# Sheet_1_2023-02-11.net
KiCad netlist of a schematic drawn in Altium Designer
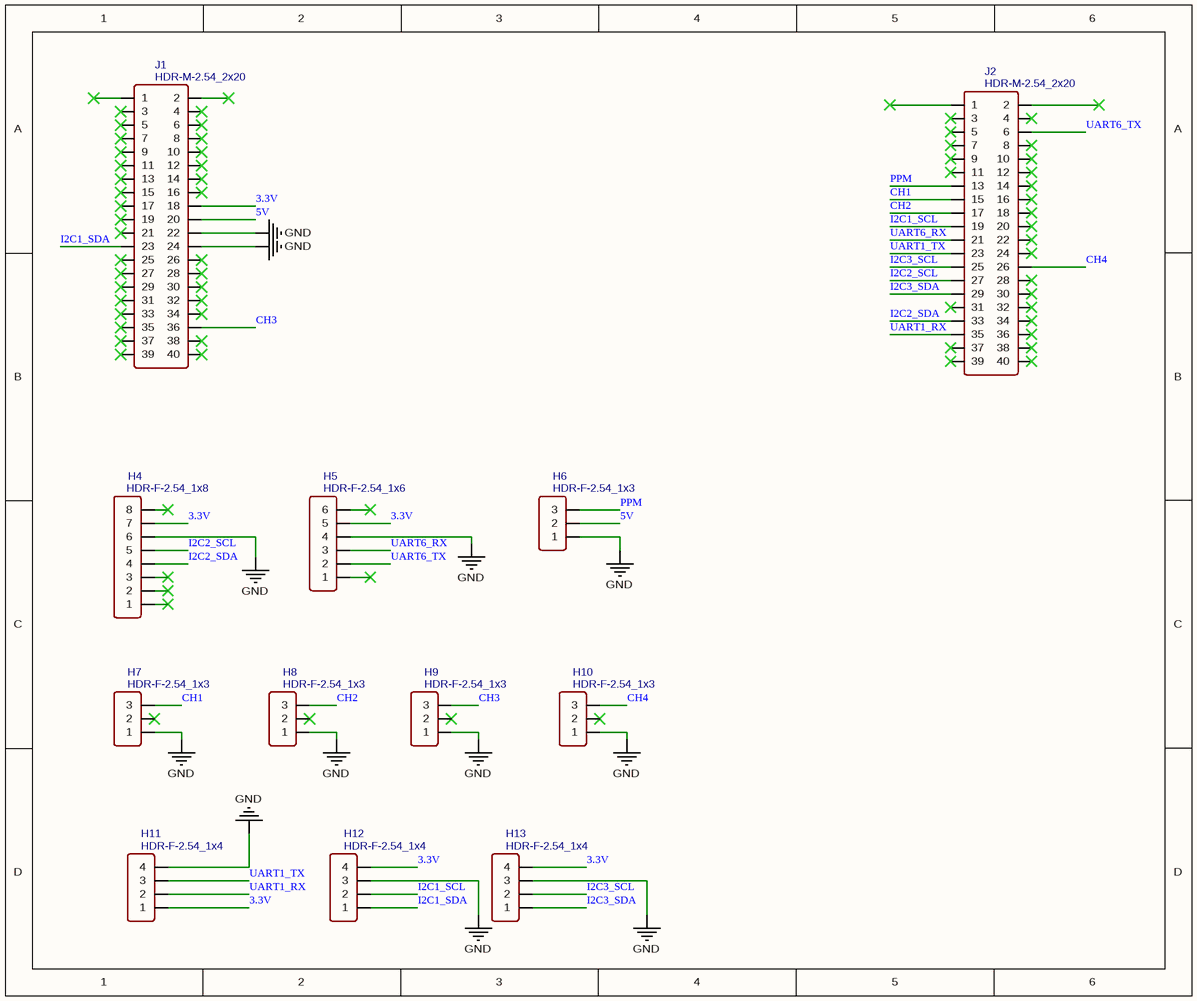
[diagram p0: Sheet_1_2023-02-11.schdoc]

(export (version "E")
  (design (tool "Eeschema 10.0.6"))
  (components
    (comp (ref "H4")
      (value "HDR-F-2.54_1x8")
      (fields (field (name "BOM_SUPPLIER PART") "C225505") (field (name "CONTRIBUTOR") "LCEDA_Lib"))
      (libsource (lib "altium-import") (part "root_2_HDR-F-2.54_1x8_"))
    )
    (comp (ref "H5")
      (value "HDR-F-2.54_1x6")
      (fields (field (name "BOM_SUPPLIER PART") "C40877") (field (name "CONTRIBUTOR") "LCEDA_Lib"))
      (libsource (lib "altium-import") (part "root_2_HDR-F-2.54_1x6_"))
    )
    (comp (ref "H6")
      (value "HDR-F-2.54_1x3")
      (fields (field (name "BOM_SUPPLIER PART") "C146690") (field (name "CONTRIBUTOR") "LCEDA_Lib"))
      (libsource (lib "altium-import") (part "root_2_HDR-F-2.54_1x3_"))
    )
    (comp (ref "H7")
      (value "HDR-F-2.54_1x3")
      (fields (field (name "BOM_SUPPLIER PART") "C146690") (field (name "CONTRIBUTOR") "LCEDA_Lib"))
      (libsource (lib "altium-import") (part "root_2_HDR-F-2.54_1x3_"))
    )
    (comp (ref "H8")
      (value "HDR-F-2.54_1x3")
      (fields (field (name "BOM_SUPPLIER PART") "C146690") (field (name "CONTRIBUTOR") "LCEDA_Lib"))
      (libsource (lib "altium-import") (part "root_2_HDR-F-2.54_1x3_"))
    )
    (comp (ref "H9")
      (value "HDR-F-2.54_1x3")
      (fields (field (name "BOM_SUPPLIER PART") "C146690") (field (name "CONTRIBUTOR") "LCEDA_Lib"))
      (libsource (lib "altium-import") (part "root_2_HDR-F-2.54_1x3_"))
    )
    (comp (ref "H10")
      (value "HDR-F-2.54_1x3")
      (fields (field (name "BOM_SUPPLIER PART") "C146690") (field (name "CONTRIBUTOR") "LCEDA_Lib"))
      (libsource (lib "altium-import") (part "root_2_HDR-F-2.54_1x3_"))
    )
    (comp (ref "H11")
      (value "HDR-F-2.54_1x4")
      (fields (field (name "BOM_SUPPLIER PART") "C225501") (field (name "CONTRIBUTOR") "LCEDA_Lib"))
      (libsource (lib "altium-import") (part "root_2_HDR-F-2.54_1x4_"))
    )
    (comp (ref "H12")
      (value "HDR-F-2.54_1x4")
      (fields (field (name "BOM_SUPPLIER PART") "C225501") (field (name "CONTRIBUTOR") "LCEDA_Lib"))
      (libsource (lib "altium-import") (part "root_2_HDR-F-2.54_1x4_"))
    )
    (comp (ref "H13")
      (value "HDR-F-2.54_1x4")
      (fields (field (name "BOM_SUPPLIER PART") "C225501") (field (name "CONTRIBUTOR") "LCEDA_Lib"))
      (libsource (lib "altium-import") (part "root_2_HDR-F-2.54_1x4_"))
    )
    (comp (ref "J1")
      (value "HDR-M-2.54_2x20")
      (fields (field (name "BOM_SUPPLIER PART") "C50980") (field (name "CONTRIBUTOR") "LCEDA_Lib"))
      (libsource (lib "altium-import") (part "root_0_HDR-M-2.54_2x20_"))
    )
    (comp (ref "J2")
      (value "HDR-M-2.54_2x20")
      (fields (field (name "BOM_SUPPLIER PART") "C50980") (field (name "CONTRIBUTOR") "LCEDA_Lib"))
      (libsource (lib "altium-import") (part "root_0_HDR-M-2.54_2x20_"))
    )
  )
  (nets
    (net (code "1") (name "/3.3V") (class "Default")
      (node (ref "H11") (pin "1") (pinfunction "1_1") (pintype "passive"))
      (node (ref "H12") (pin "4") (pinfunction "4_4") (pintype "passive"))
      (node (ref "H13") (pin "4") (pinfunction "4_4") (pintype "passive"))
      (node (ref "H4") (pin "7") (pinfunction "7_7") (pintype "passive"))
      (node (ref "H5") (pin "5") (pinfunction "5_5") (pintype "passive"))
      (node (ref "J1") (pin "18") (pinfunction "18_18") (pintype "passive"))
    )
    (net (code "2") (name "/5V") (class "Default")
      (node (ref "H6") (pin "2") (pinfunction "2_2") (pintype "passive"))
      (node (ref "J1") (pin "20") (pinfunction "20_20") (pintype "passive"))
    )
    (net (code "3") (name "/CH1") (class "Default")
      (node (ref "H7") (pin "3") (pinfunction "3_3") (pintype "passive"))
      (node (ref "J2") (pin "15") (pinfunction "15_15") (pintype "passive"))
    )
    (net (code "4") (name "/CH2") (class "Default")
      (node (ref "H8") (pin "3") (pinfunction "3_3") (pintype "passive"))
      (node (ref "J2") (pin "17") (pinfunction "17_17") (pintype "passive"))
    )
    (net (code "5") (name "/CH3") (class "Default")
      (node (ref "H9") (pin "3") (pinfunction "3_3") (pintype "passive"))
      (node (ref "J1") (pin "36") (pinfunction "36_36") (pintype "passive"))
    )
    (net (code "6") (name "/CH4") (class "Default")
      (node (ref "H10") (pin "3") (pinfunction "3_3") (pintype "passive"))
      (node (ref "J2") (pin "26") (pinfunction "26_26") (pintype "passive"))
    )
    (net (code "7") (name "/I2C1_SCL") (class "Default")
      (node (ref "H12") (pin "2") (pinfunction "2_2") (pintype "passive"))
      (node (ref "J2") (pin "19") (pinfunction "19_19") (pintype "passive"))
    )
    (net (code "8") (name "/I2C1_SDA") (class "Default")
      (node (ref "H12") (pin "1") (pinfunction "1_1") (pintype "passive"))
      (node (ref "J1") (pin "23") (pinfunction "23_23") (pintype "passive"))
    )
    (net (code "9") (name "/I2C2_SCL") (class "Default")
      (node (ref "H4") (pin "5") (pinfunction "5_5") (pintype "passive"))
      (node (ref "J2") (pin "27") (pinfunction "27_27") (pintype "passive"))
    )
    (net (code "10") (name "/I2C2_SDA") (class "Default")
      (node (ref "H4") (pin "4") (pinfunction "4_4") (pintype "passive"))
      (node (ref "J2") (pin "33") (pinfunction "33_33") (pintype "passive"))
    )
    (net (code "11") (name "/I2C3_SCL") (class "Default")
      (node (ref "H13") (pin "2") (pinfunction "2_2") (pintype "passive"))
      (node (ref "J2") (pin "25") (pinfunction "25_25") (pintype "passive"))
    )
    (net (code "12") (name "/I2C3_SDA") (class "Default")
      (node (ref "H13") (pin "1") (pinfunction "1_1") (pintype "passive"))
      (node (ref "J2") (pin "29") (pinfunction "29_29") (pintype "passive"))
    )
    (net (code "13") (name "/PPM") (class "Default")
      (node (ref "H6") (pin "3") (pinfunction "3_3") (pintype "passive"))
      (node (ref "J2") (pin "13") (pinfunction "13_13") (pintype "passive"))
    )
    (net (code "14") (name "/UART1_RX") (class "Default")
      (node (ref "H11") (pin "2") (pinfunction "2_2") (pintype "passive"))
      (node (ref "J2") (pin "35") (pinfunction "35_35") (pintype "passive"))
    )
    (net (code "15") (name "/UART1_TX") (class "Default")
      (node (ref "H11") (pin "3") (pinfunction "3_3") (pintype "passive"))
      (node (ref "J2") (pin "23") (pinfunction "23_23") (pintype "passive"))
    )
    (net (code "16") (name "/UART6_RX") (class "Default")
      (node (ref "H5") (pin "3") (pinfunction "3_3") (pintype "passive"))
      (node (ref "J2") (pin "21") (pinfunction "21_21") (pintype "passive"))
    )
    (net (code "17") (name "/UART6_TX") (class "Default")
      (node (ref "H5") (pin "2") (pinfunction "2_2") (pintype "passive"))
      (node (ref "J2") (pin "6") (pinfunction "6_6") (pintype "passive"))
    )
    (net (code "18") (name "GND") (class "Default")
      (node (ref "H10") (pin "1") (pinfunction "1_1") (pintype "passive"))
      (node (ref "H11") (pin "4") (pinfunction "4_4") (pintype "passive"))
      (node (ref "H12") (pin "3") (pinfunction "3_3") (pintype "passive"))
      (node (ref "H13") (pin "3") (pinfunction "3_3") (pintype "passive"))
      (node (ref "H4") (pin "6") (pinfunction "6_6") (pintype "passive"))
      (node (ref "H5") (pin "4") (pinfunction "4_4") (pintype "passive"))
      (node (ref "H6") (pin "1") (pinfunction "1_1") (pintype "passive"))
      (node (ref "H7") (pin "1") (pinfunction "1_1") (pintype "passive"))
      (node (ref "H8") (pin "1") (pinfunction "1_1") (pintype "passive"))
      (node (ref "H9") (pin "1") (pinfunction "1_1") (pintype "passive"))
      (node (ref "J1") (pin "22") (pinfunction "22_22") (pintype "passive"))
      (node (ref "J1") (pin "24") (pinfunction "24_24") (pintype "passive"))
    )
    (net (code "19") (name "unconnected-(H4-Pad1)") (class "Default")
      (node (ref "H4") (pin "1") (pinfunction "1_1") (pintype "passive+no_connect"))
    )
    (net (code "20") (name "unconnected-(H4-Pad2)") (class "Default")
      (node (ref "H4") (pin "2") (pinfunction "2_2") (pintype "passive+no_connect"))
    )
    (net (code "21") (name "unconnected-(H4-Pad3)") (class "Default")
      (node (ref "H4") (pin "3") (pinfunction "3_3") (pintype "passive+no_connect"))
    )
    (net (code "22") (name "unconnected-(H4-Pad8)") (class "Default")
      (node (ref "H4") (pin "8") (pinfunction "8_8") (pintype "passive+no_connect"))
    )
    (net (code "23") (name "unconnected-(H5-Pad1)") (class "Default")
      (node (ref "H5") (pin "1") (pinfunction "1_1") (pintype "passive+no_connect"))
    )
    (net (code "24") (name "unconnected-(H5-Pad6)") (class "Default")
      (node (ref "H5") (pin "6") (pinfunction "6_6") (pintype "passive+no_connect"))
    )
    (net (code "25") (name "unconnected-(H7-Pad2)") (class "Default")
      (node (ref "H7") (pin "2") (pinfunction "2_2") (pintype "passive+no_connect"))
    )
    (net (code "26") (name "unconnected-(H8-Pad2)") (class "Default")
      (node (ref "H8") (pin "2") (pinfunction "2_2") (pintype "passive+no_connect"))
    )
    (net (code "27") (name "unconnected-(H9-Pad2)") (class "Default")
      (node (ref "H9") (pin "2") (pinfunction "2_2") (pintype "passive+no_connect"))
    )
    (net (code "28") (name "unconnected-(H10-Pad2)") (class "Default")
      (node (ref "H10") (pin "2") (pinfunction "2_2") (pintype "passive+no_connect"))
    )
    (net (code "29") (name "unconnected-(J1-Pad1)") (class "Default")
      (node (ref "J1") (pin "1") (pinfunction "1_1") (pintype "passive+no_connect"))
    )
    (net (code "30") (name "unconnected-(J1-Pad2)") (class "Default")
      (node (ref "J1") (pin "2") (pinfunction "2_2") (pintype "passive+no_connect"))
    )
    (net (code "31") (name "unconnected-(J1-Pad3)") (class "Default")
      (node (ref "J1") (pin "3") (pinfunction "3_3") (pintype "passive+no_connect"))
    )
    (net (code "32") (name "unconnected-(J1-Pad4)") (class "Default")
      (node (ref "J1") (pin "4") (pinfunction "4_4") (pintype "passive+no_connect"))
    )
    (net (code "33") (name "unconnected-(J1-Pad5)") (class "Default")
      (node (ref "J1") (pin "5") (pinfunction "5_5") (pintype "passive+no_connect"))
    )
    (net (code "34") (name "unconnected-(J1-Pad6)") (class "Default")
      (node (ref "J1") (pin "6") (pinfunction "6_6") (pintype "passive+no_connect"))
    )
    (net (code "35") (name "unconnected-(J1-Pad7)") (class "Default")
      (node (ref "J1") (pin "7") (pinfunction "7_7") (pintype "passive+no_connect"))
    )
    (net (code "36") (name "unconnected-(J1-Pad8)") (class "Default")
      (node (ref "J1") (pin "8") (pinfunction "8_8") (pintype "passive+no_connect"))
    )
    (net (code "37") (name "unconnected-(J1-Pad9)") (class "Default")
      (node (ref "J1") (pin "9") (pinfunction "9_9") (pintype "passive+no_connect"))
    )
    (net (code "38") (name "unconnected-(J1-Pad10)") (class "Default")
      (node (ref "J1") (pin "10") (pinfunction "10_10") (pintype "passive+no_connect"))
    )
    (net (code "39") (name "unconnected-(J1-Pad11)") (class "Default")
      (node (ref "J1") (pin "11") (pinfunction "11_11") (pintype "passive+no_connect"))
    )
    (net (code "40") (name "unconnected-(J1-Pad12)") (class "Default")
      (node (ref "J1") (pin "12") (pinfunction "12_12") (pintype "passive+no_connect"))
    )
    (net (code "41") (name "unconnected-(J1-Pad13)") (class "Default")
      (node (ref "J1") (pin "13") (pinfunction "13_13") (pintype "passive+no_connect"))
    )
    (net (code "42") (name "unconnected-(J1-Pad14)") (class "Default")
      (node (ref "J1") (pin "14") (pinfunction "14_14") (pintype "passive+no_connect"))
    )
    (net (code "43") (name "unconnected-(J1-Pad15)") (class "Default")
      (node (ref "J1") (pin "15") (pinfunction "15_15") (pintype "passive+no_connect"))
    )
    (net (code "44") (name "unconnected-(J1-Pad16)") (class "Default")
      (node (ref "J1") (pin "16") (pinfunction "16_16") (pintype "passive+no_connect"))
    )
    (net (code "45") (name "unconnected-(J1-Pad17)") (class "Default")
      (node (ref "J1") (pin "17") (pinfunction "17_17") (pintype "passive+no_connect"))
    )
    (net (code "46") (name "unconnected-(J1-Pad19)") (class "Default")
      (node (ref "J1") (pin "19") (pinfunction "19_19") (pintype "passive+no_connect"))
    )
    (net (code "47") (name "unconnected-(J1-Pad21)") (class "Default")
      (node (ref "J1") (pin "21") (pinfunction "21_21") (pintype "passive+no_connect"))
    )
    (net (code "48") (name "unconnected-(J1-Pad25)") (class "Default")
      (node (ref "J1") (pin "25") (pinfunction "25_25") (pintype "passive+no_connect"))
    )
    (net (code "49") (name "unconnected-(J1-Pad26)") (class "Default")
      (node (ref "J1") (pin "26") (pinfunction "26_26") (pintype "passive+no_connect"))
    )
    (net (code "50") (name "unconnected-(J1-Pad27)") (class "Default")
      (node (ref "J1") (pin "27") (pinfunction "27_27") (pintype "passive+no_connect"))
    )
    (net (code "51") (name "unconnected-(J1-Pad28)") (class "Default")
      (node (ref "J1") (pin "28") (pinfunction "28_28") (pintype "passive+no_connect"))
    )
    (net (code "52") (name "unconnected-(J1-Pad29)") (class "Default")
      (node (ref "J1") (pin "29") (pinfunction "29_29") (pintype "passive+no_connect"))
    )
    (net (code "53") (name "unconnected-(J1-Pad30)") (class "Default")
      (node (ref "J1") (pin "30") (pinfunction "30_30") (pintype "passive+no_connect"))
    )
    (net (code "54") (name "unconnected-(J1-Pad31)") (class "Default")
      (node (ref "J1") (pin "31") (pinfunction "31_31") (pintype "passive+no_connect"))
    )
    (net (code "55") (name "unconnected-(J1-Pad32)") (class "Default")
      (node (ref "J1") (pin "32") (pinfunction "32_32") (pintype "passive+no_connect"))
    )
    (net (code "56") (name "unconnected-(J1-Pad33)") (class "Default")
      (node (ref "J1") (pin "33") (pinfunction "33_33") (pintype "passive+no_connect"))
    )
    (net (code "57") (name "unconnected-(J1-Pad34)") (class "Default")
      (node (ref "J1") (pin "34") (pinfunction "34_34") (pintype "passive+no_connect"))
    )
    (net (code "58") (name "unconnected-(J1-Pad35)") (class "Default")
      (node (ref "J1") (pin "35") (pinfunction "35_35") (pintype "passive+no_connect"))
    )
    (net (code "59") (name "unconnected-(J1-Pad37)") (class "Default")
      (node (ref "J1") (pin "37") (pinfunction "37_37") (pintype "passive+no_connect"))
    )
    (net (code "60") (name "unconnected-(J1-Pad38)") (class "Default")
      (node (ref "J1") (pin "38") (pinfunction "38_38") (pintype "passive+no_connect"))
    )
    (net (code "61") (name "unconnected-(J1-Pad39)") (class "Default")
      (node (ref "J1") (pin "39") (pinfunction "39_39") (pintype "passive+no_connect"))
    )
    (net (code "62") (name "unconnected-(J1-Pad40)") (class "Default")
      (node (ref "J1") (pin "40") (pinfunction "40_40") (pintype "passive+no_connect"))
    )
    (net (code "63") (name "unconnected-(J2-Pad1)") (class "Default")
      (node (ref "J2") (pin "1") (pinfunction "1_1") (pintype "passive+no_connect"))
    )
    (net (code "64") (name "unconnected-(J2-Pad2)") (class "Default")
      (node (ref "J2") (pin "2") (pinfunction "2_2") (pintype "passive+no_connect"))
    )
    (net (code "65") (name "unconnected-(J2-Pad3)") (class "Default")
      (node (ref "J2") (pin "3") (pinfunction "3_3") (pintype "passive+no_connect"))
    )
    (net (code "66") (name "unconnected-(J2-Pad4)") (class "Default")
      (node (ref "J2") (pin "4") (pinfunction "4_4") (pintype "passive+no_connect"))
    )
    (net (code "67") (name "unconnected-(J2-Pad5)") (class "Default")
      (node (ref "J2") (pin "5") (pinfunction "5_5") (pintype "passive+no_connect"))
    )
    (net (code "68") (name "unconnected-(J2-Pad7)") (class "Default")
      (node (ref "J2") (pin "7") (pinfunction "7_7") (pintype "passive+no_connect"))
    )
    (net (code "69") (name "unconnected-(J2-Pad8)") (class "Default")
      (node (ref "J2") (pin "8") (pinfunction "8_8") (pintype "passive+no_connect"))
    )
    (net (code "70") (name "unconnected-(J2-Pad9)") (class "Default")
      (node (ref "J2") (pin "9") (pinfunction "9_9") (pintype "passive+no_connect"))
    )
    (net (code "71") (name "unconnected-(J2-Pad10)") (class "Default")
      (node (ref "J2") (pin "10") (pinfunction "10_10") (pintype "passive+no_connect"))
    )
    (net (code "72") (name "unconnected-(J2-Pad11)") (class "Default")
      (node (ref "J2") (pin "11") (pinfunction "11_11") (pintype "passive+no_connect"))
    )
    (net (code "73") (name "unconnected-(J2-Pad12)") (class "Default")
      (node (ref "J2") (pin "12") (pinfunction "12_12") (pintype "passive+no_connect"))
    )
    (net (code "74") (name "unconnected-(J2-Pad14)") (class "Default")
      (node (ref "J2") (pin "14") (pinfunction "14_14") (pintype "passive+no_connect"))
    )
    (net (code "75") (name "unconnected-(J2-Pad16)") (class "Default")
      (node (ref "J2") (pin "16") (pinfunction "16_16") (pintype "passive+no_connect"))
    )
    (net (code "76") (name "unconnected-(J2-Pad18)") (class "Default")
      (node (ref "J2") (pin "18") (pinfunction "18_18") (pintype "passive+no_connect"))
    )
    (net (code "77") (name "unconnected-(J2-Pad20)") (class "Default")
      (node (ref "J2") (pin "20") (pinfunction "20_20") (pintype "passive+no_connect"))
    )
    (net (code "78") (name "unconnected-(J2-Pad22)") (class "Default")
      (node (ref "J2") (pin "22") (pinfunction "22_22") (pintype "passive+no_connect"))
    )
    (net (code "79") (name "unconnected-(J2-Pad24)") (class "Default")
      (node (ref "J2") (pin "24") (pinfunction "24_24") (pintype "passive+no_connect"))
    )
    (net (code "80") (name "unconnected-(J2-Pad28)") (class "Default")
      (node (ref "J2") (pin "28") (pinfunction "28_28") (pintype "passive+no_connect"))
    )
    (net (code "81") (name "unconnected-(J2-Pad30)") (class "Default")
      (node (ref "J2") (pin "30") (pinfunction "30_30") (pintype "passive+no_connect"))
    )
    (net (code "82") (name "unconnected-(J2-Pad31)") (class "Default")
      (node (ref "J2") (pin "31") (pinfunction "31_31") (pintype "passive+no_connect"))
    )
    (net (code "83") (name "unconnected-(J2-Pad32)") (class "Default")
      (node (ref "J2") (pin "32") (pinfunction "32_32") (pintype "passive+no_connect"))
    )
    (net (code "84") (name "unconnected-(J2-Pad34)") (class "Default")
      (node (ref "J2") (pin "34") (pinfunction "34_34") (pintype "passive+no_connect"))
    )
    (net (code "85") (name "unconnected-(J2-Pad36)") (class "Default")
      (node (ref "J2") (pin "36") (pinfunction "36_36") (pintype "passive+no_connect"))
    )
    (net (code "86") (name "unconnected-(J2-Pad37)") (class "Default")
      (node (ref "J2") (pin "37") (pinfunction "37_37") (pintype "passive+no_connect"))
    )
    (net (code "87") (name "unconnected-(J2-Pad38)") (class "Default")
      (node (ref "J2") (pin "38") (pinfunction "38_38") (pintype "passive+no_connect"))
    )
    (net (code "88") (name "unconnected-(J2-Pad39)") (class "Default")
      (node (ref "J2") (pin "39") (pinfunction "39_39") (pintype "passive+no_connect"))
    )
    (net (code "89") (name "unconnected-(J2-Pad40)") (class "Default")
      (node (ref "J2") (pin "40") (pinfunction "40_40") (pintype "passive+no_connect"))
    )
  )
)
